# 1_WIRING.net
KiCad netlist of a schematic drawn in Altium Designer
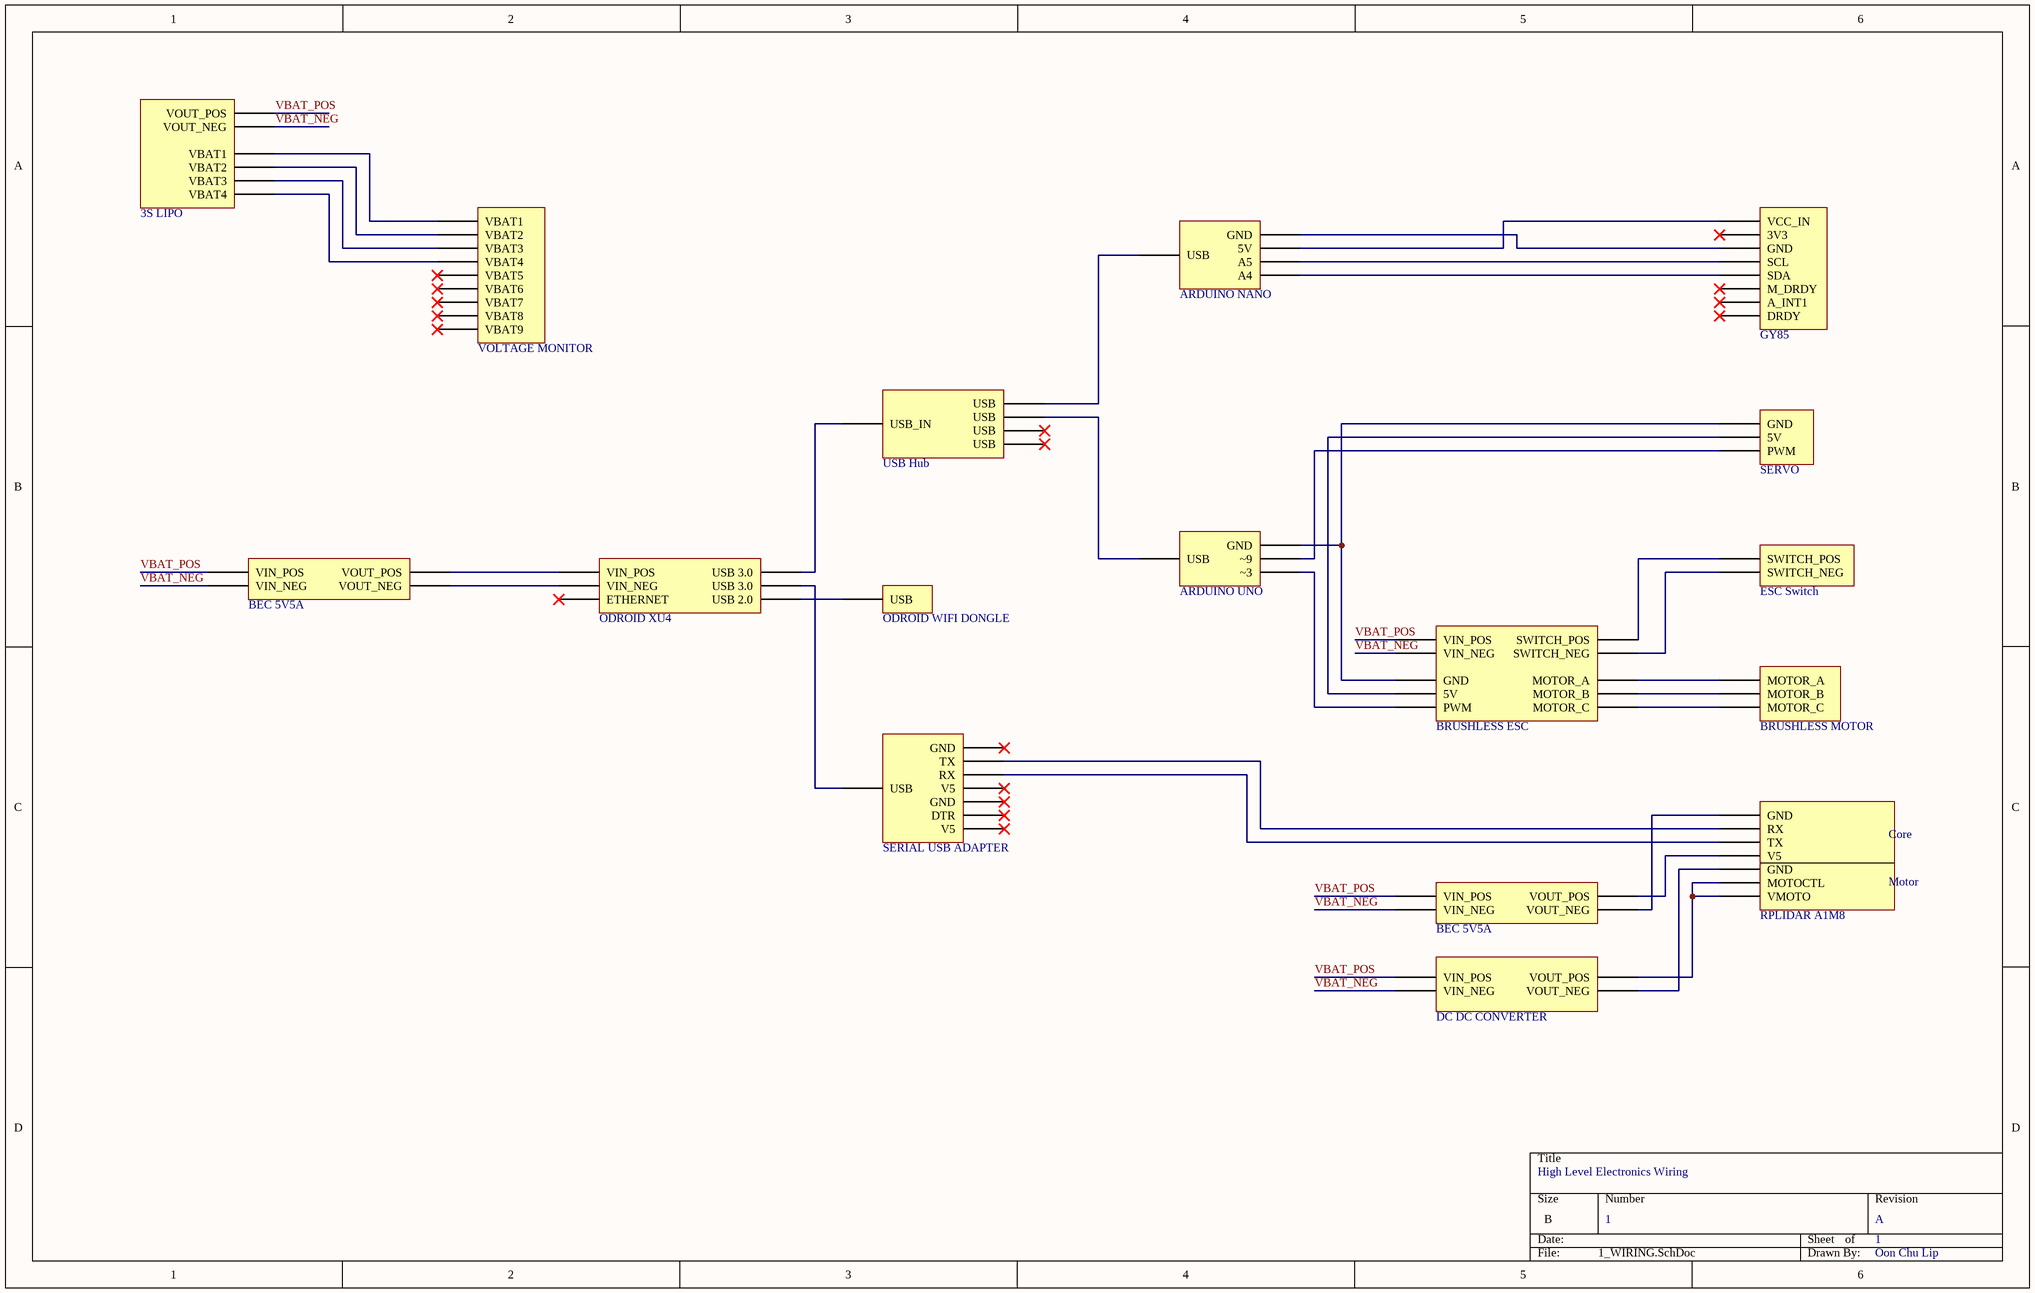
[diagram p0: 1_WIRING.SchDoc]

(export (version "E")
  (design (tool "Eeschema 10.0.6"))
  (components
    (comp (ref "*")
      (value "ESC Switch")
      (libsource (lib "HIGH_LEVEL_ELECTRONICS_INT_LIB") (part "ESC Switch"))
    )
    (comp (ref "H1")
      (value "VOLTAGE MONITOR")
      (libsource (lib "HIGH_LEVEL_ELECTRONICS_INT_LIB") (part "Voltage Monitor"))
    )
    (comp (ref "H2") (value "GY85") (libsource (lib "HIGH_LEVEL_ELECTRONICS_INT_LIB") (part "IMU")))
    (comp (ref "H3")
      (value "ARDUINO NANO")
      (libsource (lib "HIGH_LEVEL_ELECTRONICS_INT_LIB") (part "Arduino Nano"))
    )
    (comp (ref "H4")
      (value "USB Hub")
      (description "USB HUB")
      (libsource (lib "HIGH_LEVEL_ELECTRONICS_INT_LIB") (part "USB Hub"))
    )
    (comp (ref "H5") (value "SERVO") (libsource (lib "HIGH_LEVEL_ELECTRONICS_INT_LIB") (part "Servo")))
    (comp (ref "H6")
      (value "ARDUINO UNO")
      (libsource (lib "HIGH_LEVEL_ELECTRONICS_INT_LIB") (part "Arduino UNO"))
    )
    (comp (ref "H7") (value "BEC 5V5A") (libsource (lib "HIGH_LEVEL_ELECTRONICS_INT_LIB") (part "BEC")))
    (comp (ref "H8")
      (value "ODROID XU4")
      (libsource (lib "HIGH_LEVEL_ELECTRONICS_INT_LIB") (part "Computer"))
    )
    (comp (ref "H9")
      (value "ODROID WIFI DONGLE")
      (libsource (lib "HIGH_LEVEL_ELECTRONICS_INT_LIB") (part "Wifi Dongle"))
    )
    (comp (ref "H10") (value "BRUSHLESS ESC") (libsource (lib "HIGH_LEVEL_ELECTRONICS_INT_LIB") (part "ESC")))
    (comp (ref "H11")
      (value "SERIAL USB ADAPTER")
      (libsource (lib "HIGH_LEVEL_ELECTRONICS_INT_LIB") (part "Serial USB Adapter"))
    )
    (comp (ref "H12")
      (value "RPLIDAR A1M8")
      (libsource (lib "HIGH_LEVEL_ELECTRONICS_INT_LIB") (part "Lidar"))
    )
    (comp (ref "H13") (value "BEC 5V5A") (libsource (lib "HIGH_LEVEL_ELECTRONICS_INT_LIB") (part "BEC")))
    (comp (ref "H14")
      (value "DC DC CONVERTER")
      (libsource (lib "HIGH_LEVEL_ELECTRONICS_INT_LIB") (part "DC DC Converter"))
    )
    (comp (ref "M1")
      (value "BRUSHLESS MOTOR")
      (libsource (lib "HIGH_LEVEL_ELECTRONICS_INT_LIB") (part "Brushless Motor"))
    )
    (comp (ref "PS1") (value "3S LIPO") (libsource (lib "HIGH_LEVEL_ELECTRONICS_INT_LIB") (part "Battery")))
  )
  (nets
    (net (code "1") (name "/VBAT_NEG") (class "Default")
      (node (ref "H10") (pin "2") (pinfunction "VIN_NEG_2") (pintype "passive"))
      (node (ref "H13") (pin "2") (pinfunction "VIN_NEG_2") (pintype "passive"))
      (node (ref "H14") (pin "2") (pinfunction "VIN_NEG_2") (pintype "passive"))
      (node (ref "H7") (pin "2") (pinfunction "VIN_NEG_2") (pintype "passive"))
      (node (ref "PS1") (pin "2") (pinfunction "VOUT_NEG_2") (pintype "passive"))
    )
    (net (code "2") (name "/VBAT_POS") (class "Default")
      (node (ref "H10") (pin "1") (pinfunction "VIN_POS_1") (pintype "passive"))
      (node (ref "H13") (pin "1") (pinfunction "VIN_POS_1") (pintype "passive"))
      (node (ref "H14") (pin "1") (pinfunction "VIN_POS_1") (pintype "passive"))
      (node (ref "H7") (pin "1") (pinfunction "VIN_POS_1") (pintype "passive"))
      (node (ref "PS1") (pin "1") (pinfunction "VOUT_POS_1") (pintype "passive"))
    )
    (net (code "3") (name "Net-(*-SWITCH_NEG)") (class "Default")
      (node (ref "*") (pin "2") (pinfunction "SWITCH_NEG_2") (pintype "passive"))
      (node (ref "H10") (pin "10") (pinfunction "SWITCH_NEG_10") (pintype "passive"))
    )
    (net (code "4") (name "Net-(*-SWITCH_POS)") (class "Default")
      (node (ref "*") (pin "1") (pinfunction "SWITCH_POS_1") (pintype "passive"))
      (node (ref "H10") (pin "9") (pinfunction "SWITCH_POS_9") (pintype "passive"))
    )
    (net (code "5") (name "Net-(H1-VBAT1)") (class "Default")
      (node (ref "H1") (pin "1") (pinfunction "VBAT1_1") (pintype "passive"))
      (node (ref "PS1") (pin "3") (pinfunction "VBAT1_3") (pintype "passive"))
    )
    (net (code "6") (name "Net-(H1-VBAT2)") (class "Default")
      (node (ref "H1") (pin "2") (pinfunction "VBAT2_2") (pintype "passive"))
      (node (ref "PS1") (pin "4") (pinfunction "VBAT2_4") (pintype "passive"))
    )
    (net (code "7") (name "Net-(H1-VBAT3)") (class "Default")
      (node (ref "H1") (pin "3") (pinfunction "VBAT3_3") (pintype "passive"))
      (node (ref "PS1") (pin "5") (pinfunction "VBAT3_5") (pintype "passive"))
    )
    (net (code "8") (name "Net-(H1-VBAT4)") (class "Default")
      (node (ref "H1") (pin "4") (pinfunction "VBAT4_4") (pintype "passive"))
      (node (ref "PS1") (pin "6") (pinfunction "VBAT4_6") (pintype "passive"))
    )
    (net (code "9") (name "Net-(H2-GND)") (class "Default")
      (node (ref "H2") (pin "3") (pinfunction "GND_3") (pintype "passive"))
      (node (ref "H3") (pin "2") (pinfunction "GND_2") (pintype "passive"))
    )
    (net (code "10") (name "Net-(H2-SCL)") (class "Default")
      (node (ref "H2") (pin "4") (pinfunction "SCL_4") (pintype "passive"))
      (node (ref "H3") (pin "4") (pinfunction "A5_4") (pintype "passive"))
    )
    (net (code "11") (name "Net-(H2-SDA)") (class "Default")
      (node (ref "H2") (pin "5") (pinfunction "SDA_5") (pintype "passive"))
      (node (ref "H3") (pin "5") (pinfunction "A4_5") (pintype "passive"))
    )
    (net (code "12") (name "Net-(H2-VCC_IN)") (class "Default")
      (node (ref "H2") (pin "1") (pinfunction "VCC_IN_1") (pintype "passive"))
      (node (ref "H3") (pin "3") (pinfunction "5V_3") (pintype "passive"))
    )
    (net (code "13") (name "Net-(H3-USB)") (class "Default")
      (node (ref "H3") (pin "1") (pinfunction "USB_1") (pintype "passive"))
      (node (ref "H4") (pin "2") (pinfunction "USB_2") (pintype "passive"))
    )
    (net (code "14") (name "Net-(H4-USB_IN)") (class "Default")
      (node (ref "H4") (pin "1") (pinfunction "USB_IN_1") (pintype "passive"))
      (node (ref "H8") (pin "3") (pinfunction "USB_3.0_3") (pintype "passive"))
    )
    (net (code "15") (name "Net-(H5-PWM)") (class "Default")
      (node (ref "H5") (pin "3") (pinfunction "PWM_3") (pintype "passive"))
      (node (ref "H6") (pin "3") (pinfunction "~9_3") (pintype "passive"))
    )
    (net (code "16") (name "Net-(H6-USB)") (class "Default")
      (node (ref "H4") (pin "3") (pinfunction "USB_3") (pintype "passive"))
      (node (ref "H6") (pin "1") (pinfunction "USB_1") (pintype "passive"))
    )
    (net (code "17") (name "Net-(H7-VOUT_NEG)") (class "Default")
      (node (ref "H7") (pin "4") (pinfunction "VOUT_NEG_4") (pintype "passive"))
      (node (ref "H8") (pin "2") (pinfunction "VIN_NEG_2") (pintype "passive"))
    )
    (net (code "18") (name "Net-(H7-VOUT_POS)") (class "Default")
      (node (ref "H7") (pin "3") (pinfunction "VOUT_POS_3") (pintype "passive"))
      (node (ref "H8") (pin "1") (pinfunction "VIN_POS_1") (pintype "passive"))
    )
    (net (code "19") (name "Net-(H8-USB_2.0)") (class "Default")
      (node (ref "H8") (pin "5") (pinfunction "USB_2.0_5") (pintype "passive"))
      (node (ref "H9") (pin "1") (pinfunction "USB_1") (pintype "passive"))
    )
    (net (code "20") (name "Net-(H10-5V)") (class "Default")
      (node (ref "H10") (pin "4") (pinfunction "5V_4") (pintype "passive"))
      (node (ref "H5") (pin "2") (pinfunction "5V_2") (pintype "passive"))
    )
    (net (code "21") (name "Net-(H10-GND)") (class "Default")
      (node (ref "H10") (pin "3") (pinfunction "GND_3") (pintype "passive"))
      (node (ref "H5") (pin "1") (pinfunction "GND_1") (pintype "passive"))
      (node (ref "H6") (pin "2") (pinfunction "GND_2") (pintype "passive"))
    )
    (net (code "22") (name "Net-(H10-MOTOR_A)") (class "Default")
      (node (ref "H10") (pin "6") (pinfunction "MOTOR_A_6") (pintype "passive"))
      (node (ref "M1") (pin "1") (pinfunction "MOTOR_A_1") (pintype "passive"))
    )
    (net (code "23") (name "Net-(H10-MOTOR_B)") (class "Default")
      (node (ref "H10") (pin "7") (pinfunction "MOTOR_B_7") (pintype "passive"))
      (node (ref "M1") (pin "2") (pinfunction "MOTOR_B_2") (pintype "passive"))
    )
    (net (code "24") (name "Net-(H10-MOTOR_C)") (class "Default")
      (node (ref "H10") (pin "8") (pinfunction "MOTOR_C_8") (pintype "passive"))
      (node (ref "M1") (pin "3") (pinfunction "MOTOR_C_3") (pintype "passive"))
    )
    (net (code "25") (name "Net-(H10-PWM)") (class "Default")
      (node (ref "H10") (pin "5") (pinfunction "PWM_5") (pintype "passive"))
      (node (ref "H6") (pin "4") (pinfunction "~3_4") (pintype "passive"))
    )
    (net (code "26") (name "Net-(H11-RX)") (class "Default")
      (node (ref "H11") (pin "3") (pinfunction "RX_3") (pintype "passive"))
      (node (ref "H12") (pin "5") (pinfunction "TX_5") (pintype "passive"))
    )
    (net (code "27") (name "Net-(H11-TX)") (class "Default")
      (node (ref "H11") (pin "2") (pinfunction "TX_2") (pintype "passive"))
      (node (ref "H12") (pin "6") (pinfunction "RX_6") (pintype "passive"))
    )
    (net (code "28") (name "Net-(H11-USB)") (class "Default")
      (node (ref "H11") (pin "8") (pinfunction "USB_8") (pintype "passive"))
      (node (ref "H8") (pin "4") (pinfunction "USB_3.0_4") (pintype "passive"))
    )
    (net (code "29") (name "Net-(H12-MOTOCTL)") (class "Default")
      (node (ref "H12") (pin "1") (pinfunction "VMOTO_1") (pintype "passive"))
      (node (ref "H12") (pin "2") (pinfunction "MOTOCTL_2") (pintype "passive"))
      (node (ref "H14") (pin "3") (pinfunction "VOUT_POS_3") (pintype "passive"))
    )
    (net (code "30") (name "Net-(H12-V5)") (class "Default")
      (node (ref "H12") (pin "4") (pinfunction "V5_4") (pintype "passive"))
      (node (ref "H13") (pin "3") (pinfunction "VOUT_POS_3") (pintype "passive"))
    )
    (net (code "31") (name "Net-(H13-VOUT_NEG)") (class "Default")
      (node (ref "H12") (pin "7") (pinfunction "GND_7") (pintype "passive"))
      (node (ref "H13") (pin "4") (pinfunction "VOUT_NEG_4") (pintype "passive"))
    )
    (net (code "32") (name "Net-(H14-VOUT_NEG)") (class "Default")
      (node (ref "H12") (pin "3") (pinfunction "GND_3") (pintype "passive"))
      (node (ref "H14") (pin "4") (pinfunction "VOUT_NEG_4") (pintype "passive"))
    )
    (net (code "33") (name "unconnected-(H1-VBAT5-Pad5)") (class "Default")
      (node (ref "H1") (pin "5") (pinfunction "VBAT5_5") (pintype "passive+no_connect"))
    )
    (net (code "34") (name "unconnected-(H1-VBAT6-Pad6)") (class "Default")
      (node (ref "H1") (pin "6") (pinfunction "VBAT6_6") (pintype "passive+no_connect"))
    )
    (net (code "35") (name "unconnected-(H1-VBAT7-Pad7)") (class "Default")
      (node (ref "H1") (pin "7") (pinfunction "VBAT7_7") (pintype "passive+no_connect"))
    )
    (net (code "36") (name "unconnected-(H1-VBAT8-Pad8)") (class "Default")
      (node (ref "H1") (pin "8") (pinfunction "VBAT8_8") (pintype "passive+no_connect"))
    )
    (net (code "37") (name "unconnected-(H1-VBAT9-Pad9)") (class "Default")
      (node (ref "H1") (pin "9") (pinfunction "VBAT9_9") (pintype "passive+no_connect"))
    )
    (net (code "38") (name "unconnected-(H2-3V3-Pad2)") (class "Default")
      (node (ref "H2") (pin "2") (pinfunction "3V3_2") (pintype "passive+no_connect"))
    )
    (net (code "39") (name "unconnected-(H2-A_INT1-Pad7)") (class "Default")
      (node (ref "H2") (pin "7") (pinfunction "A_INT1_7") (pintype "passive+no_connect"))
    )
    (net (code "40") (name "unconnected-(H2-DRDY-Pad8)") (class "Default")
      (node (ref "H2") (pin "8") (pinfunction "DRDY_8") (pintype "passive+no_connect"))
    )
    (net (code "41") (name "unconnected-(H2-M_DRDY-Pad6)") (class "Default")
      (node (ref "H2") (pin "6") (pinfunction "M_DRDY_6") (pintype "passive+no_connect"))
    )
    (net (code "42") (name "unconnected-(H4-USB-Pad4)") (class "Default")
      (node (ref "H4") (pin "4") (pinfunction "USB_4") (pintype "passive+no_connect"))
    )
    (net (code "43") (name "unconnected-(H4-USB-Pad5)") (class "Default")
      (node (ref "H4") (pin "5") (pinfunction "USB_5") (pintype "passive+no_connect"))
    )
    (net (code "44") (name "unconnected-(H8-ETHERNET-Pad6)") (class "Default")
      (node (ref "H8") (pin "6") (pinfunction "ETHERNET_6") (pintype "passive+no_connect"))
    )
    (net (code "45") (name "unconnected-(H11-DTR-Pad6)") (class "Default")
      (node (ref "H11") (pin "6") (pinfunction "DTR_6") (pintype "passive+no_connect"))
    )
    (net (code "46") (name "unconnected-(H11-GND-Pad1)") (class "Default")
      (node (ref "H11") (pin "1") (pinfunction "GND_1") (pintype "passive+no_connect"))
    )
    (net (code "47") (name "unconnected-(H11-GND-Pad5)") (class "Default")
      (node (ref "H11") (pin "5") (pinfunction "GND_5") (pintype "passive+no_connect"))
    )
    (net (code "48") (name "unconnected-(H11-V5-Pad4)") (class "Default")
      (node (ref "H11") (pin "4") (pinfunction "V5_4") (pintype "passive+no_connect"))
    )
    (net (code "49") (name "unconnected-(H11-V5-Pad7)") (class "Default")
      (node (ref "H11") (pin "7") (pinfunction "V5_7") (pintype "passive+no_connect"))
    )
  )
)
